# RP2350.net
KiCad netlist of a schematic drawn in EasyEDA Pro
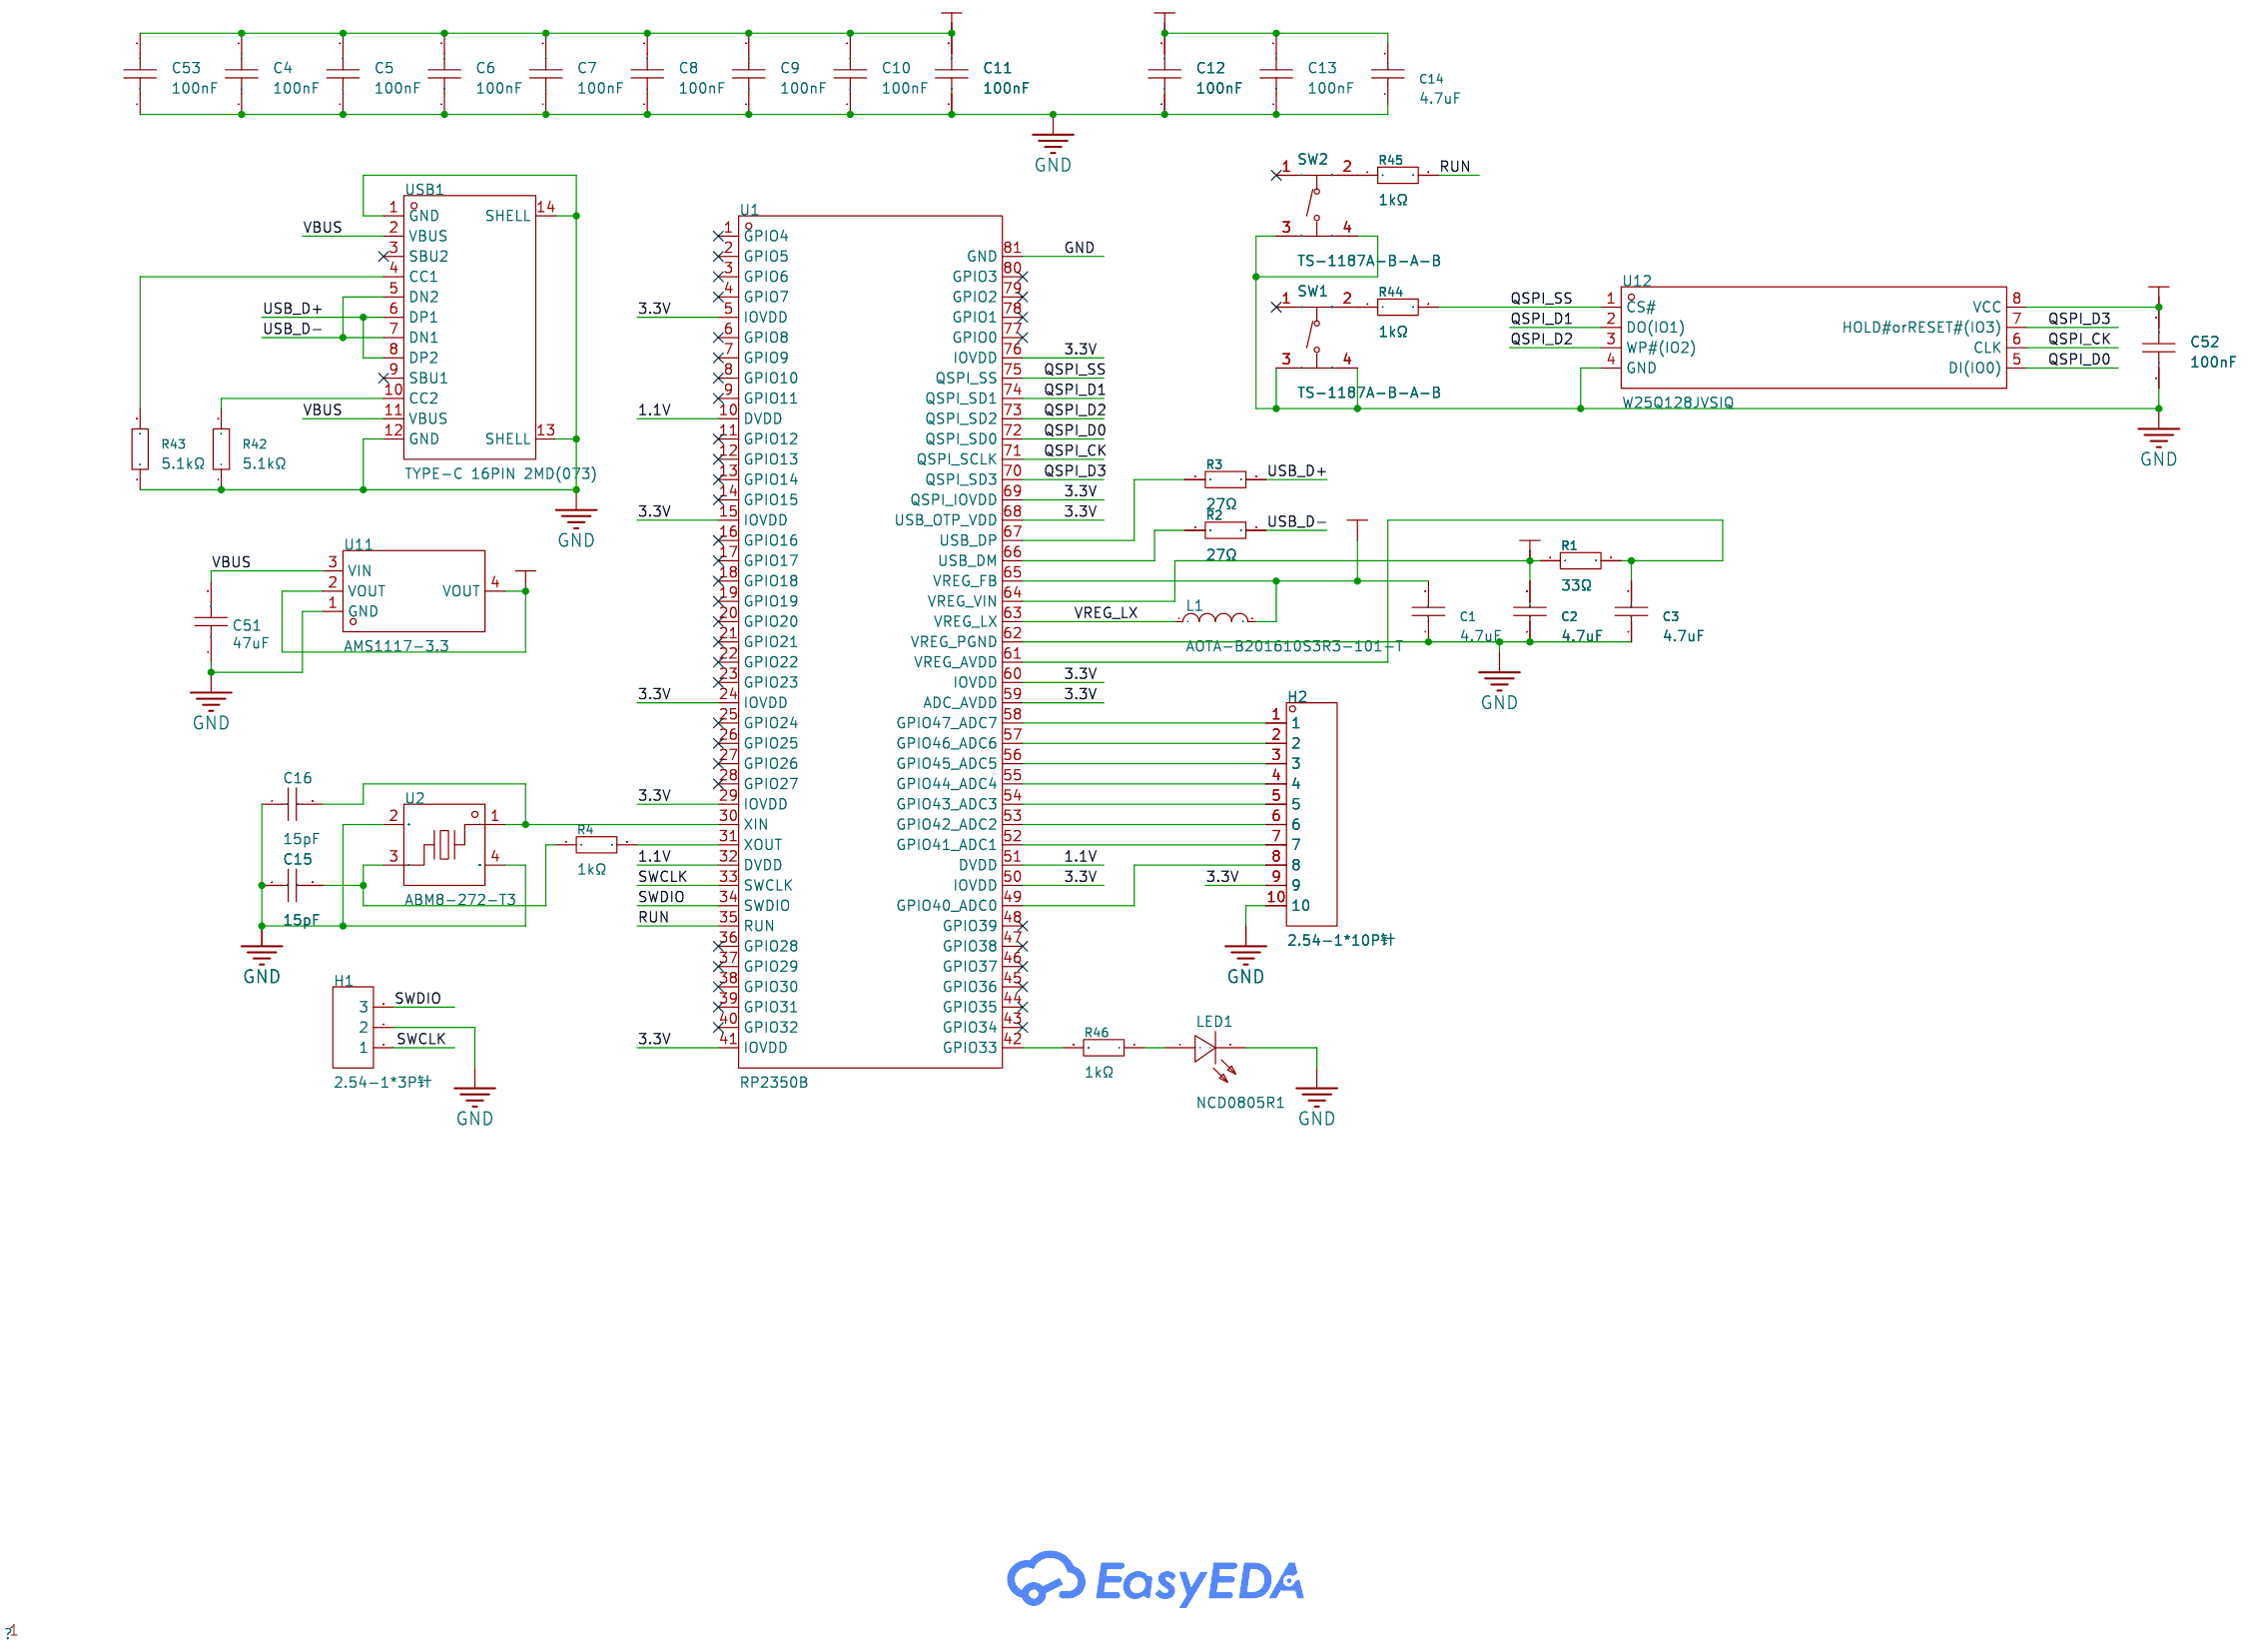
[diagram p0: schematic sheet]

(export (version "E")
  (design (tool "Eeschema 10.0.6"))
  (components
    (comp (ref "C1")
      (value "4.7uF")
      (footprint "easyedapro:C0402")
      (fields
        (field (name "Manufacturer Part") "CL05A475MP5NRNC")
        (field (name "Manufacturer") "SAMSUNG(三星)")
      )
      (libsource (lib "easyedapro") (part "CL05A475MP5NRNC"))
    )
    (comp (ref "C2")
      (value "4.7uF")
      (footprint "easyedapro:C0402")
      (fields
        (field (name "Manufacturer Part") "CL05A475MP5NRNC")
        (field (name "Manufacturer") "SAMSUNG(三星)")
      )
      (libsource (lib "easyedapro") (part "CL05A475MP5NRNC"))
    )
    (comp (ref "C3")
      (value "4.7uF")
      (footprint "easyedapro:C0402")
      (fields
        (field (name "Manufacturer Part") "CL05A475MP5NRNC")
        (field (name "Manufacturer") "SAMSUNG(三星)")
      )
      (libsource (lib "easyedapro") (part "CL05A475MP5NRNC"))
    )
    (comp (ref "C4")
      (value "100nF")
      (footprint "easyedapro:C0402")
      (fields
        (field (name "Manufacturer Part") "CL05B104KO5NNNC")
        (field (name "Manufacturer") "SAMSUNG(三星)")
      )
      (libsource (lib "easyedapro") (part "CL05B104KO5NNNC"))
    )
    (comp (ref "C5")
      (value "100nF")
      (footprint "easyedapro:C0402")
      (fields
        (field (name "Manufacturer Part") "CL05B104KO5NNNC")
        (field (name "Manufacturer") "SAMSUNG(三星)")
      )
      (libsource (lib "easyedapro") (part "CL05B104KO5NNNC"))
    )
    (comp (ref "C6")
      (value "100nF")
      (footprint "easyedapro:C0402")
      (fields
        (field (name "Manufacturer Part") "CL05B104KO5NNNC")
        (field (name "Manufacturer") "SAMSUNG(三星)")
      )
      (libsource (lib "easyedapro") (part "CL05B104KO5NNNC"))
    )
    (comp (ref "C7")
      (value "100nF")
      (footprint "easyedapro:C0402")
      (fields
        (field (name "Manufacturer Part") "CL05B104KO5NNNC")
        (field (name "Manufacturer") "SAMSUNG(三星)")
      )
      (libsource (lib "easyedapro") (part "CL05B104KO5NNNC"))
    )
    (comp (ref "C8")
      (value "100nF")
      (footprint "easyedapro:C0402")
      (fields
        (field (name "Manufacturer Part") "CL05B104KO5NNNC")
        (field (name "Manufacturer") "SAMSUNG(三星)")
      )
      (libsource (lib "easyedapro") (part "CL05B104KO5NNNC"))
    )
    (comp (ref "C9")
      (value "100nF")
      (footprint "easyedapro:C0402")
      (fields
        (field (name "Manufacturer Part") "CL05B104KO5NNNC")
        (field (name "Manufacturer") "SAMSUNG(三星)")
      )
      (libsource (lib "easyedapro") (part "CL05B104KO5NNNC"))
    )
    (comp (ref "C10")
      (value "100nF")
      (footprint "easyedapro:C0402")
      (fields
        (field (name "Manufacturer Part") "CL05B104KO5NNNC")
        (field (name "Manufacturer") "SAMSUNG(三星)")
      )
      (libsource (lib "easyedapro") (part "CL05B104KO5NNNC"))
    )
    (comp (ref "C11")
      (value "100nF")
      (footprint "easyedapro:C0402")
      (fields
        (field (name "Manufacturer Part") "CL05B104KO5NNNC")
        (field (name "Manufacturer") "SAMSUNG(三星)")
      )
      (libsource (lib "easyedapro") (part "CL05B104KO5NNNC"))
    )
    (comp (ref "C12")
      (value "100nF")
      (footprint "easyedapro:C0402")
      (fields
        (field (name "Manufacturer Part") "CL05B104KO5NNNC")
        (field (name "Manufacturer") "SAMSUNG(三星)")
      )
      (libsource (lib "easyedapro") (part "CL05B104KO5NNNC"))
    )
    (comp (ref "C13")
      (value "100nF")
      (footprint "easyedapro:C0402")
      (fields
        (field (name "Manufacturer Part") "CL05B104KO5NNNC")
        (field (name "Manufacturer") "SAMSUNG(三星)")
      )
      (libsource (lib "easyedapro") (part "CL05B104KO5NNNC"))
    )
    (comp (ref "C14")
      (value "4.7uF")
      (footprint "easyedapro:C0402")
      (fields
        (field (name "Manufacturer Part") "CL05A475MP5NRNC")
        (field (name "Manufacturer") "SAMSUNG(三星)")
      )
      (libsource (lib "easyedapro") (part "CL05A475MP5NRNC"))
    )
    (comp (ref "C15")
      (value "15pF")
      (footprint "easyedapro:C0402")
      (fields (field (name "Manufacturer Part") "0402CG150J500NT") (field (name "Manufacturer") "FH(风华)"))
      (libsource (lib "easyedapro") (part "0402CG150J500NT"))
    )
    (comp (ref "C16")
      (value "15pF")
      (footprint "easyedapro:C0402")
      (fields (field (name "Manufacturer Part") "0402CG150J500NT") (field (name "Manufacturer") "FH(风华)"))
      (libsource (lib "easyedapro") (part "0402CG150J500NT"))
    )
    (comp (ref "C51")
      (value "47uF")
      (footprint "easyedapro:C1206")
      (fields (field (name "Manufacturer Part") "CL31A476MPHNNNE") (field (name "Manufacturer") "SAMSUNG"))
      (libsource (lib "easyedapro") (part "47uF"))
    )
    (comp (ref "C52")
      (value "100nF")
      (footprint "easyedapro:C0402")
      (fields
        (field (name "Manufacturer Part") "CL05B104KO5NNNC")
        (field (name "Manufacturer") "SAMSUNG(三星)")
      )
      (libsource (lib "easyedapro") (part "CL05B104KO5NNNC"))
    )
    (comp (ref "C53")
      (value "100nF")
      (footprint "easyedapro:C0402")
      (fields
        (field (name "Manufacturer Part") "CL05B104KO5NNNC")
        (field (name "Manufacturer") "SAMSUNG(三星)")
      )
      (libsource (lib "easyedapro") (part "CL05B104KO5NNNC"))
    )
    (comp (ref "H1")
      (value "2.54-1*3P针")
      (footprint "easyedapro:HDR-TH_3P-P2.54-V-M-1")
      (fields (field (name "Manufacturer") "BOOMELE(博穆精密)"))
      (libsource (lib "easyedapro") (part "Header-Male-2.54_1x3"))
    )
    (comp (ref "H2")
      (value "2.54-1*10P针")
      (footprint "easyedapro:HDR-TH_10P-P2.54-V-M-1")
      (fields (field (name "Manufacturer") "BOOMELE(博穆精密)"))
      (libsource (lib "easyedapro") (part "Header-Male-2.54_1x10"))
    )
    (comp (ref "L1")
      (value "AOTA-B201610S3R3-101-T")
      (footprint "easyedapro:IND-SMD_L2.0-W1.6_AOTA-B201610S3R3-101-T")
      (fields (field (name "Manufacturer") "ABRACON"))
      (libsource (lib "easyedapro") (part "AOTA-B201610S3R3-101-T"))
    )
    (comp (ref "LED1")
      (value "NCD0805R1")
      (footprint "easyedapro:LED0805-R-RD")
      (fields (field (name "Manufacturer") "国星光电"))
      (libsource (lib "easyedapro") (part "FC-2012HRK-620D"))
    )
    (comp (ref "R1")
      (value "33Ω")
      (footprint "easyedapro:R0402")
      (fields
        (field (name "Manufacturer Part") "0402WGF330JTCE")
        (field (name "Manufacturer") "UNI-ROYAL(厚声)")
      )
      (libsource (lib "easyedapro") (part "0402WGF330JTCE"))
    )
    (comp (ref "R2")
      (value "27Ω")
      (footprint "easyedapro:R0402")
      (fields
        (field (name "Manufacturer Part") "0402WGF270JTCE")
        (field (name "Manufacturer") "UNI-ROYAL(厚声)")
      )
      (libsource (lib "easyedapro") (part "0402WGF270JTCE"))
    )
    (comp (ref "R3")
      (value "27Ω")
      (footprint "easyedapro:R0402")
      (fields (field (name "Manufacturer Part") "F") (field (name "Manufacturer") "UNI-ROYAL(厚声)"))
      (libsource (lib "easyedapro") (part "0402WGF270JTCE"))
    )
    (comp (ref "R4")
      (value "1kΩ")
      (footprint "easyedapro:R0402")
      (fields
        (field (name "Manufacturer Part") "0402WGF1001TCE")
        (field (name "Manufacturer") "UNI-ROYAL(厚声)")
      )
      (libsource (lib "easyedapro") (part "0402WGF1001TCE"))
    )
    (comp (ref "R42")
      (value "5.1kΩ")
      (footprint "easyedapro:R0402")
      (fields
        (field (name "Manufacturer Part") "0402WGF5101TCE")
        (field (name "Manufacturer") "UNI-ROYAL(厚声)")
      )
      (libsource (lib "easyedapro") (part "0402WGF5101TCE"))
    )
    (comp (ref "R43")
      (value "5.1kΩ")
      (footprint "easyedapro:R0402")
      (fields
        (field (name "Manufacturer Part") "0402WGF5101TCE")
        (field (name "Manufacturer") "UNI-ROYAL(厚声)")
      )
      (libsource (lib "easyedapro") (part "0402WGF5101TCE"))
    )
    (comp (ref "R44")
      (value "1kΩ")
      (footprint "easyedapro:R0402")
      (fields
        (field (name "Manufacturer Part") "0402WGF1001TCE")
        (field (name "Manufacturer") "UNI-ROYAL(厚声)")
      )
      (libsource (lib "easyedapro") (part "0402WGF1001TCE"))
    )
    (comp (ref "R45")
      (value "1kΩ")
      (footprint "easyedapro:R0402")
      (fields
        (field (name "Manufacturer Part") "0402WGF1001TCE")
        (field (name "Manufacturer") "UNI-ROYAL(厚声)")
      )
      (libsource (lib "easyedapro") (part "0402WGF1001TCE"))
    )
    (comp (ref "R46")
      (value "1kΩ")
      (footprint "easyedapro:R0402")
      (fields
        (field (name "Manufacturer Part") "0402WGF1001TCE")
        (field (name "Manufacturer") "UNI-ROYAL(厚声)")
      )
      (libsource (lib "easyedapro") (part "0402WGF1001TCE"))
    )
    (comp (ref "SW1")
      (value "TS-1187A-B-A-B")
      (footprint "easyedapro:SW-SMD_4P-L5.1-W5.1-P3.70-LS6.5-TL_H1.5")
      (fields (field (name "Manufacturer") "XKB Connectivity(中国星坤)"))
      (libsource (lib "easyedapro") (part "TS-1187A-B-A-B"))
    )
    (comp (ref "SW2")
      (value "TS-1187A-B-A-B")
      (footprint "easyedapro:SW-SMD_4P-L5.1-W5.1-P3.70-LS6.5-TL_H1.5")
      (fields (field (name "Manufacturer") "XKB Connectivity(中国星坤)"))
      (libsource (lib "easyedapro") (part "TS-1187A-B-A-B"))
    )
    (comp (ref "U1")
      (value "RP2350B")
      (footprint "easyedapro:QFN-80_L10.0-W10.0-P0.40-TL-EP3.4")
      (fields (field (name "Manufacturer") "Raspberry Pi(树莓派)"))
      (libsource (lib "easyedapro") (part "RP2350B_C42415655"))
    )
    (comp (ref "U2")
      (value "ABM8-272-T3")
      (footprint "easyedapro:CRYSTAL-SMD_4P-L3.2-W2.5-BL")
      (fields (field (name "Manufacturer") "ABRACON"))
      (libsource (lib "easyedapro") (part "ABM8-272-T3_C20625731"))
    )
    (comp (ref "U11")
      (value "AMS1117-3.3")
      (footprint "easyedapro:SOT-223-3_L6.5-W3.4-P2.30-LS7.0-BR")
      (fields (field (name "Manufacturer") "AMS"))
      (libsource (lib "easyedapro") (part "AMS1117-3.3"))
    )
    (comp (ref "U12")
      (value "W25Q128JVSIQ")
      (footprint "easyedapro:SOIC-8_L5.3-W5.3-P1.27-LS8.0-BL")
      (fields (field (name "Manufacturer") "WINBOND(华邦)"))
      (libsource (lib "easyedapro") (part "W25Q128JVSIQ"))
    )
    (comp (ref "USB1")
      (value "TYPE-C 16PIN 2MD(073)")
      (footprint "easyedapro:USB-C-SMD_TYPE-C-6PIN-2MD-073")
      (fields (field (name "Manufacturer") "SHOU HAN(首韩)"))
      (libsource (lib "easyedapro") (part "TYPE-C 16PIN 2MD(073)"))
    )
  )
  (nets
    (net (code "1") (name "/QSPI_CK") (class "Default")
      (node (ref "U1") (pin "71") (pinfunction "QSPI_SCLK_71") (pintype "unspecified"))
      (node (ref "U12") (pin "6") (pinfunction "CLK_6") (pintype "unspecified"))
    )
    (net (code "2") (name "/QSPI_D0") (class "Default")
      (node (ref "U1") (pin "72") (pinfunction "QSPI_SD0_72") (pintype "unspecified"))
      (node (ref "U12") (pin "5") (pinfunction "DI(IO0)_5") (pintype "unspecified"))
    )
    (net (code "3") (name "/QSPI_D1") (class "Default")
      (node (ref "U1") (pin "74") (pinfunction "QSPI_SD1_74") (pintype "unspecified"))
      (node (ref "U12") (pin "2") (pinfunction "DO(IO1)_2") (pintype "unspecified"))
    )
    (net (code "4") (name "/QSPI_D2") (class "Default")
      (node (ref "U1") (pin "73") (pinfunction "QSPI_SD2_73") (pintype "unspecified"))
      (node (ref "U12") (pin "3") (pinfunction "WP#(IO2)_3") (pintype "unspecified"))
    )
    (net (code "5") (name "/QSPI_D3") (class "Default")
      (node (ref "U1") (pin "70") (pinfunction "QSPI_SD3_70") (pintype "unspecified"))
      (node (ref "U12") (pin "7") (pinfunction "HOLD#orRESET#(IO3)_7") (pintype "unspecified"))
    )
    (net (code "6") (name "/QSPI_SS") (class "Default")
      (node (ref "R44") (pin "2") (pinfunction "2_2") (pintype "input"))
      (node (ref "U1") (pin "75") (pinfunction "QSPI_SS_75") (pintype "unspecified"))
      (node (ref "U12") (pin "1") (pinfunction "CS#_1") (pintype "unspecified"))
    )
    (net (code "7") (name "/RUN") (class "Default")
      (node (ref "R45") (pin "2") (pinfunction "2_2") (pintype "input"))
      (node (ref "U1") (pin "35") (pinfunction "RUN_35") (pintype "unspecified"))
    )
    (net (code "8") (name "/SWCLK") (class "Default")
      (node (ref "H1") (pin "1") (pinfunction "1_1") (pintype "input"))
      (node (ref "U1") (pin "33") (pinfunction "SWCLK_33") (pintype "unspecified"))
    )
    (net (code "9") (name "/SWDIO") (class "Default")
      (node (ref "H1") (pin "3") (pinfunction "3_3") (pintype "input"))
      (node (ref "U1") (pin "34") (pinfunction "SWDIO_34") (pintype "unspecified"))
    )
    (net (code "10") (name "/USB_D+") (class "Default")
      (node (ref "R3") (pin "2") (pinfunction "2_2") (pintype "input"))
      (node (ref "USB1") (pin "6") (pinfunction "DP1_6") (pintype "unspecified"))
      (node (ref "USB1") (pin "8") (pinfunction "DP2_8") (pintype "unspecified"))
    )
    (net (code "11") (name "/USB_D-") (class "Default")
      (node (ref "R2") (pin "2") (pinfunction "2_2") (pintype "input"))
      (node (ref "USB1") (pin "5") (pinfunction "DN2_5") (pintype "unspecified"))
      (node (ref "USB1") (pin "7") (pinfunction "DN1_7") (pintype "unspecified"))
    )
    (net (code "12") (name "/VBUS") (class "Default")
      (node (ref "C51") (pin "2") (pinfunction "2_2") (pintype "unspecified"))
      (node (ref "U11") (pin "3") (pinfunction "VIN_3") (pintype "unspecified"))
      (node (ref "USB1") (pin "11") (pinfunction "VBUS_11") (pintype "unspecified"))
      (node (ref "USB1") (pin "2") (pinfunction "VBUS_2") (pintype "unspecified"))
    )
    (net (code "13") (name "/VREG_LX") (class "Default")
      (node (ref "L1") (pin "1") (pinfunction "1_1") (pintype "unspecified"))
      (node (ref "U1") (pin "63") (pinfunction "VREG_LX_63") (pintype "unspecified"))
    )
    (net (code "14") (name "1.1V") (class "Default")
      (node (ref "C1") (pin "2") (pinfunction "2_2") (pintype "input"))
      (node (ref "C12") (pin "2") (pinfunction "2_2") (pintype "unspecified"))
      (node (ref "C13") (pin "2") (pinfunction "2_2") (pintype "unspecified"))
      (node (ref "C14") (pin "2") (pinfunction "2_2") (pintype "input"))
      (node (ref "L1") (pin "2") (pinfunction "2_2") (pintype "unspecified"))
      (node (ref "U1") (pin "10") (pinfunction "DVDD_10") (pintype "unspecified"))
      (node (ref "U1") (pin "32") (pinfunction "DVDD_32") (pintype "unspecified"))
      (node (ref "U1") (pin "51") (pinfunction "DVDD_51") (pintype "unspecified"))
      (node (ref "U1") (pin "65") (pinfunction "VREG_FB_65") (pintype "unspecified"))
    )
    (net (code "15") (name "3.3V") (class "Default")
      (node (ref "C10") (pin "2") (pinfunction "2_2") (pintype "unspecified"))
      (node (ref "C11") (pin "2") (pinfunction "2_2") (pintype "unspecified"))
      (node (ref "C2") (pin "2") (pinfunction "2_2") (pintype "input"))
      (node (ref "C4") (pin "2") (pinfunction "2_2") (pintype "unspecified"))
      (node (ref "C5") (pin "2") (pinfunction "2_2") (pintype "unspecified"))
      (node (ref "C52") (pin "2") (pinfunction "2_2") (pintype "unspecified"))
      (node (ref "C53") (pin "2") (pinfunction "2_2") (pintype "unspecified"))
      (node (ref "C6") (pin "2") (pinfunction "2_2") (pintype "unspecified"))
      (node (ref "C7") (pin "2") (pinfunction "2_2") (pintype "unspecified"))
      (node (ref "C8") (pin "2") (pinfunction "2_2") (pintype "unspecified"))
      (node (ref "C9") (pin "2") (pinfunction "2_2") (pintype "unspecified"))
      (node (ref "H2") (pin "9") (pinfunction "9_9") (pintype "input"))
      (node (ref "R1") (pin "1") (pinfunction "1_1") (pintype "input"))
      (node (ref "U1") (pin "15") (pinfunction "IOVDD_15") (pintype "unspecified"))
      (node (ref "U1") (pin "24") (pinfunction "IOVDD_24") (pintype "unspecified"))
      (node (ref "U1") (pin "29") (pinfunction "IOVDD_29") (pintype "unspecified"))
      (node (ref "U1") (pin "41") (pinfunction "IOVDD_41") (pintype "unspecified"))
      (node (ref "U1") (pin "5") (pinfunction "IOVDD_5") (pintype "unspecified"))
      (node (ref "U1") (pin "50") (pinfunction "IOVDD_50") (pintype "unspecified"))
      (node (ref "U1") (pin "59") (pinfunction "ADC_AVDD_59") (pintype "unspecified"))
      (node (ref "U1") (pin "60") (pinfunction "IOVDD_60") (pintype "unspecified"))
      (node (ref "U1") (pin "64") (pinfunction "VREG_VIN_64") (pintype "unspecified"))
      (node (ref "U1") (pin "68") (pinfunction "USB_OTP_VDD_68") (pintype "unspecified"))
      (node (ref "U1") (pin "69") (pinfunction "QSPI_IOVDD_69") (pintype "unspecified"))
      (node (ref "U1") (pin "76") (pinfunction "IOVDD_76") (pintype "unspecified"))
      (node (ref "U11") (pin "2") (pinfunction "VOUT_2") (pintype "unspecified"))
      (node (ref "U11") (pin "4") (pinfunction "VOUT_4") (pintype "unspecified"))
      (node (ref "U12") (pin "8") (pinfunction "VCC_8") (pintype "unspecified"))
    )
    (net (code "16") (name "GND") (class "Default")
      (node (ref "C1") (pin "1") (pinfunction "1_1") (pintype "input"))
      (node (ref "C10") (pin "1") (pinfunction "1_1") (pintype "unspecified"))
      (node (ref "C11") (pin "1") (pinfunction "1_1") (pintype "unspecified"))
      (node (ref "C12") (pin "1") (pinfunction "1_1") (pintype "unspecified"))
      (node (ref "C13") (pin "1") (pinfunction "1_1") (pintype "unspecified"))
      (node (ref "C14") (pin "1") (pinfunction "1_1") (pintype "input"))
      (node (ref "C15") (pin "1") (pinfunction "1_1") (pintype "input"))
      (node (ref "C16") (pin "1") (pinfunction "1_1") (pintype "input"))
      (node (ref "C2") (pin "1") (pinfunction "1_1") (pintype "input"))
      (node (ref "C3") (pin "1") (pinfunction "1_1") (pintype "input"))
      (node (ref "C4") (pin "1") (pinfunction "1_1") (pintype "unspecified"))
      (node (ref "C5") (pin "1") (pinfunction "1_1") (pintype "unspecified"))
      (node (ref "C51") (pin "1") (pinfunction "1_1") (pintype "unspecified"))
      (node (ref "C52") (pin "1") (pinfunction "1_1") (pintype "unspecified"))
      (node (ref "C53") (pin "1") (pinfunction "1_1") (pintype "unspecified"))
      (node (ref "C6") (pin "1") (pinfunction "1_1") (pintype "unspecified"))
      (node (ref "C7") (pin "1") (pinfunction "1_1") (pintype "unspecified"))
      (node (ref "C8") (pin "1") (pinfunction "1_1") (pintype "unspecified"))
      (node (ref "C9") (pin "1") (pinfunction "1_1") (pintype "unspecified"))
      (node (ref "H1") (pin "2") (pinfunction "2_2") (pintype "input"))
      (node (ref "H2") (pin "10") (pinfunction "10_10") (pintype "input"))
      (node (ref "LED1") (pin "2") (pinfunction "-_2") (pintype "unspecified"))
      (node (ref "R42") (pin "1") (pinfunction "1_1") (pintype "input"))
      (node (ref "R43") (pin "1") (pinfunction "1_1") (pintype "input"))
      (node (ref "SW1") (pin "3") (pinfunction "C_3") (pintype "unspecified"))
      (node (ref "SW1") (pin "4") (pinfunction "D_4") (pintype "unspecified"))
      (node (ref "SW2") (pin "3") (pinfunction "C_3") (pintype "unspecified"))
      (node (ref "SW2") (pin "4") (pinfunction "D_4") (pintype "unspecified"))
      (node (ref "U1") (pin "62") (pinfunction "VREG_PGND_62") (pintype "unspecified"))
      (node (ref "U1") (pin "81") (pinfunction "GND_81") (pintype "unspecified"))
      (node (ref "U11") (pin "1") (pinfunction "GND_1") (pintype "unspecified"))
      (node (ref "U12") (pin "4") (pinfunction "GND_4") (pintype "unspecified"))
      (node (ref "U2") (pin "2") (pinfunction "GND_2") (pintype "input"))
      (node (ref "U2") (pin "4") (pinfunction "GND_4") (pintype "input"))
      (node (ref "USB1") (pin "1") (pinfunction "GND_1") (pintype "unspecified"))
      (node (ref "USB1") (pin "12") (pinfunction "GND_12") (pintype "unspecified"))
      (node (ref "USB1") (pin "13") (pinfunction "SHELL_13") (pintype "unspecified"))
      (node (ref "USB1") (pin "14") (pinfunction "SHELL_14") (pintype "unspecified"))
    )
    (net (code "17") (name "Net-(C15-Pad2)") (class "Default")
      (node (ref "C15") (pin "2") (pinfunction "2_2") (pintype "input"))
      (node (ref "R4") (pin "1") (pinfunction "1_1") (pintype "input"))
      (node (ref "U2") (pin "3") (pinfunction "3_3") (pintype "input"))
    )
    (net (code "18") (name "Net-(LED1-+)") (class "Default")
      (node (ref "LED1") (pin "1") (pinfunction "+_1") (pintype "unspecified"))
      (node (ref "R46") (pin "1") (pinfunction "1_1") (pintype "input"))
    )
    (net (code "19") (name "Net-(SW1-B)") (class "Default")
      (node (ref "R44") (pin "1") (pinfunction "1_1") (pintype "input"))
      (node (ref "SW1") (pin "2") (pinfunction "B_2") (pintype "unspecified"))
    )
    (net (code "20") (name "Net-(SW2-B)") (class "Default")
      (node (ref "R45") (pin "1") (pinfunction "1_1") (pintype "input"))
      (node (ref "SW2") (pin "2") (pinfunction "B_2") (pintype "unspecified"))
    )
    (net (code "21") (name "Net-(U1-GPIO33)") (class "Default")
      (node (ref "R46") (pin "2") (pinfunction "2_2") (pintype "input"))
      (node (ref "U1") (pin "42") (pinfunction "GPIO33_42") (pintype "unspecified"))
    )
    (net (code "22") (name "Net-(U1-GPIO40_ADC0)") (class "Default")
      (node (ref "H2") (pin "8") (pinfunction "8_8") (pintype "input"))
      (node (ref "U1") (pin "49") (pinfunction "GPIO40_ADC0_49") (pintype "unspecified"))
    )
    (net (code "23") (name "Net-(U1-GPIO41_ADC1)") (class "Default")
      (node (ref "H2") (pin "7") (pinfunction "7_7") (pintype "input"))
      (node (ref "U1") (pin "52") (pinfunction "GPIO41_ADC1_52") (pintype "unspecified"))
    )
    (net (code "24") (name "Net-(U1-GPIO42_ADC2)") (class "Default")
      (node (ref "H2") (pin "6") (pinfunction "6_6") (pintype "input"))
      (node (ref "U1") (pin "53") (pinfunction "GPIO42_ADC2_53") (pintype "unspecified"))
    )
    (net (code "25") (name "Net-(U1-GPIO43_ADC3)") (class "Default")
      (node (ref "H2") (pin "5") (pinfunction "5_5") (pintype "input"))
      (node (ref "U1") (pin "54") (pinfunction "GPIO43_ADC3_54") (pintype "unspecified"))
    )
    (net (code "26") (name "Net-(U1-GPIO44_ADC4)") (class "Default")
      (node (ref "H2") (pin "4") (pinfunction "4_4") (pintype "input"))
      (node (ref "U1") (pin "55") (pinfunction "GPIO44_ADC4_55") (pintype "unspecified"))
    )
    (net (code "27") (name "Net-(U1-GPIO45_ADC5)") (class "Default")
      (node (ref "H2") (pin "3") (pinfunction "3_3") (pintype "input"))
      (node (ref "U1") (pin "56") (pinfunction "GPIO45_ADC5_56") (pintype "unspecified"))
    )
    (net (code "28") (name "Net-(U1-GPIO46_ADC6)") (class "Default")
      (node (ref "H2") (pin "2") (pinfunction "2_2") (pintype "input"))
      (node (ref "U1") (pin "57") (pinfunction "GPIO46_ADC6_57") (pintype "unspecified"))
    )
    (net (code "29") (name "Net-(U1-GPIO47_ADC7)") (class "Default")
      (node (ref "H2") (pin "1") (pinfunction "1_1") (pintype "input"))
      (node (ref "U1") (pin "58") (pinfunction "GPIO47_ADC7_58") (pintype "unspecified"))
    )
    (net (code "30") (name "Net-(U1-USB_DM)") (class "Default")
      (node (ref "R2") (pin "1") (pinfunction "1_1") (pintype "input"))
      (node (ref "U1") (pin "66") (pinfunction "USB_DM_66") (pintype "unspecified"))
    )
    (net (code "31") (name "Net-(U1-USB_DP)") (class "Default")
      (node (ref "R3") (pin "1") (pinfunction "1_1") (pintype "input"))
      (node (ref "U1") (pin "67") (pinfunction "USB_DP_67") (pintype "unspecified"))
    )
    (net (code "32") (name "Net-(U1-VREG_AVDD)") (class "Default")
      (node (ref "C3") (pin "2") (pinfunction "2_2") (pintype "input"))
      (node (ref "R1") (pin "2") (pinfunction "2_2") (pintype "input"))
      (node (ref "U1") (pin "61") (pinfunction "VREG_AVDD_61") (pintype "unspecified"))
    )
    (net (code "33") (name "Net-(U1-XIN)") (class "Default")
      (node (ref "C16") (pin "2") (pinfunction "2_2") (pintype "input"))
      (node (ref "U1") (pin "30") (pinfunction "XIN_30") (pintype "unspecified"))
      (node (ref "U2") (pin "1") (pinfunction "1_1") (pintype "input"))
    )
    (net (code "34") (name "Net-(U1-XOUT)") (class "Default")
      (node (ref "R4") (pin "2") (pinfunction "2_2") (pintype "input"))
      (node (ref "U1") (pin "31") (pinfunction "XOUT_31") (pintype "unspecified"))
    )
    (net (code "35") (name "Net-(USB1-CC1)") (class "Default")
      (node (ref "R43") (pin "2") (pinfunction "2_2") (pintype "input"))
      (node (ref "USB1") (pin "4") (pinfunction "CC1_4") (pintype "unspecified"))
    )
    (net (code "36") (name "Net-(USB1-CC2)") (class "Default")
      (node (ref "R42") (pin "2") (pinfunction "2_2") (pintype "input"))
      (node (ref "USB1") (pin "10") (pinfunction "CC2_10") (pintype "unspecified"))
    )
    (net (code "37") (name "unconnected-(SW1-A-Pad1)") (class "Default")
      (node (ref "SW1") (pin "1") (pinfunction "A_1") (pintype "unspecified+no_connect"))
    )
    (net (code "38") (name "unconnected-(SW2-A-Pad1)") (class "Default")
      (node (ref "SW2") (pin "1") (pinfunction "A_1") (pintype "unspecified+no_connect"))
    )
    (net (code "39") (name "unconnected-(U1-GPIO0-Pad77)") (class "Default")
      (node (ref "U1") (pin "77") (pinfunction "GPIO0_77") (pintype "unspecified+no_connect"))
    )
    (net (code "40") (name "unconnected-(U1-GPIO1-Pad78)") (class "Default")
      (node (ref "U1") (pin "78") (pinfunction "GPIO1_78") (pintype "unspecified+no_connect"))
    )
    (net (code "41") (name "unconnected-(U1-GPIO2-Pad79)") (class "Default")
      (node (ref "U1") (pin "79") (pinfunction "GPIO2_79") (pintype "unspecified+no_connect"))
    )
    (net (code "42") (name "unconnected-(U1-GPIO3-Pad80)") (class "Default")
      (node (ref "U1") (pin "80") (pinfunction "GPIO3_80") (pintype "unspecified+no_connect"))
    )
    (net (code "43") (name "unconnected-(U1-GPIO4-Pad1)") (class "Default")
      (node (ref "U1") (pin "1") (pinfunction "GPIO4_1") (pintype "unspecified+no_connect"))
    )
    (net (code "44") (name "unconnected-(U1-GPIO5-Pad2)") (class "Default")
      (node (ref "U1") (pin "2") (pinfunction "GPIO5_2") (pintype "unspecified+no_connect"))
    )
    (net (code "45") (name "unconnected-(U1-GPIO6-Pad3)") (class "Default")
      (node (ref "U1") (pin "3") (pinfunction "GPIO6_3") (pintype "unspecified+no_connect"))
    )
    (net (code "46") (name "unconnected-(U1-GPIO7-Pad4)") (class "Default")
      (node (ref "U1") (pin "4") (pinfunction "GPIO7_4") (pintype "unspecified+no_connect"))
    )
    (net (code "47") (name "unconnected-(U1-GPIO8-Pad6)") (class "Default")
      (node (ref "U1") (pin "6") (pinfunction "GPIO8_6") (pintype "unspecified+no_connect"))
    )
    (net (code "48") (name "unconnected-(U1-GPIO9-Pad7)") (class "Default")
      (node (ref "U1") (pin "7") (pinfunction "GPIO9_7") (pintype "unspecified+no_connect"))
    )
    (net (code "49") (name "unconnected-(U1-GPIO10-Pad8)") (class "Default")
      (node (ref "U1") (pin "8") (pinfunction "GPIO10_8") (pintype "unspecified+no_connect"))
    )
    (net (code "50") (name "unconnected-(U1-GPIO11-Pad9)") (class "Default")
      (node (ref "U1") (pin "9") (pinfunction "GPIO11_9") (pintype "unspecified+no_connect"))
    )
    (net (code "51") (name "unconnected-(U1-GPIO12-Pad11)") (class "Default")
      (node (ref "U1") (pin "11") (pinfunction "GPIO12_11") (pintype "unspecified+no_connect"))
    )
    (net (code "52") (name "unconnected-(U1-GPIO13-Pad12)") (class "Default")
      (node (ref "U1") (pin "12") (pinfunction "GPIO13_12") (pintype "unspecified+no_connect"))
    )
    (net (code "53") (name "unconnected-(U1-GPIO14-Pad13)") (class "Default")
      (node (ref "U1") (pin "13") (pinfunction "GPIO14_13") (pintype "unspecified+no_connect"))
    )
    (net (code "54") (name "unconnected-(U1-GPIO15-Pad14)") (class "Default")
      (node (ref "U1") (pin "14") (pinfunction "GPIO15_14") (pintype "unspecified+no_connect"))
    )
    (net (code "55") (name "unconnected-(U1-GPIO16-Pad16)") (class "Default")
      (node (ref "U1") (pin "16") (pinfunction "GPIO16_16") (pintype "unspecified+no_connect"))
    )
    (net (code "56") (name "unconnected-(U1-GPIO17-Pad17)") (class "Default")
      (node (ref "U1") (pin "17") (pinfunction "GPIO17_17") (pintype "unspecified+no_connect"))
    )
    (net (code "57") (name "unconnected-(U1-GPIO18-Pad18)") (class "Default")
      (node (ref "U1") (pin "18") (pinfunction "GPIO18_18") (pintype "unspecified+no_connect"))
    )
    (net (code "58") (name "unconnected-(U1-GPIO19-Pad19)") (class "Default")
      (node (ref "U1") (pin "19") (pinfunction "GPIO19_19") (pintype "unspecified+no_connect"))
    )
    (net (code "59") (name "unconnected-(U1-GPIO20-Pad20)") (class "Default")
      (node (ref "U1") (pin "20") (pinfunction "GPIO20_20") (pintype "unspecified+no_connect"))
    )
    (net (code "60") (name "unconnected-(U1-GPIO21-Pad21)") (class "Default")
      (node (ref "U1") (pin "21") (pinfunction "GPIO21_21") (pintype "unspecified+no_connect"))
    )
    (net (code "61") (name "unconnected-(U1-GPIO22-Pad22)") (class "Default")
      (node (ref "U1") (pin "22") (pinfunction "GPIO22_22") (pintype "unspecified+no_connect"))
    )
    (net (code "62") (name "unconnected-(U1-GPIO23-Pad23)") (class "Default")
      (node (ref "U1") (pin "23") (pinfunction "GPIO23_23") (pintype "unspecified+no_connect"))
    )
    (net (code "63") (name "unconnected-(U1-GPIO24-Pad25)") (class "Default")
      (node (ref "U1") (pin "25") (pinfunction "GPIO24_25") (pintype "unspecified+no_connect"))
    )
    (net (code "64") (name "unconnected-(U1-GPIO25-Pad26)") (class "Default")
      (node (ref "U1") (pin "26") (pinfunction "GPIO25_26") (pintype "unspecified+no_connect"))
    )
    (net (code "65") (name "unconnected-(U1-GPIO26-Pad27)") (class "Default")
      (node (ref "U1") (pin "27") (pinfunction "GPIO26_27") (pintype "unspecified+no_connect"))
    )
    (net (code "66") (name "unconnected-(U1-GPIO27-Pad28)") (class "Default")
      (node (ref "U1") (pin "28") (pinfunction "GPIO27_28") (pintype "unspecified+no_connect"))
    )
    (net (code "67") (name "unconnected-(U1-GPIO28-Pad36)") (class "Default")
      (node (ref "U1") (pin "36") (pinfunction "GPIO28_36") (pintype "unspecified+no_connect"))
    )
    (net (code "68") (name "unconnected-(U1-GPIO29-Pad37)") (class "Default")
      (node (ref "U1") (pin "37") (pinfunction "GPIO29_37") (pintype "unspecified+no_connect"))
    )
    (net (code "69") (name "unconnected-(U1-GPIO30-Pad38)") (class "Default")
      (node (ref "U1") (pin "38") (pinfunction "GPIO30_38") (pintype "unspecified+no_connect"))
    )
    (net (code "70") (name "unconnected-(U1-GPIO31-Pad39)") (class "Default")
      (node (ref "U1") (pin "39") (pinfunction "GPIO31_39") (pintype "unspecified+no_connect"))
    )
    (net (code "71") (name "unconnected-(U1-GPIO32-Pad40)") (class "Default")
      (node (ref "U1") (pin "40") (pinfunction "GPIO32_40") (pintype "unspecified+no_connect"))
    )
    (net (code "72") (name "unconnected-(U1-GPIO34-Pad43)") (class "Default")
      (node (ref "U1") (pin "43") (pinfunction "GPIO34_43") (pintype "unspecified+no_connect"))
    )
    (net (code "73") (name "unconnected-(U1-GPIO35-Pad44)") (class "Default")
      (node (ref "U1") (pin "44") (pinfunction "GPIO35_44") (pintype "unspecified+no_connect"))
    )
    (net (code "74") (name "unconnected-(U1-GPIO36-Pad45)") (class "Default")
      (node (ref "U1") (pin "45") (pinfunction "GPIO36_45") (pintype "unspecified+no_connect"))
    )
    (net (code "75") (name "unconnected-(U1-GPIO37-Pad46)") (class "Default")
      (node (ref "U1") (pin "46") (pinfunction "GPIO37_46") (pintype "unspecified+no_connect"))
    )
    (net (code "76") (name "unconnected-(U1-GPIO38-Pad47)") (class "Default")
      (node (ref "U1") (pin "47") (pinfunction "GPIO38_47") (pintype "unspecified+no_connect"))
    )
    (net (code "77") (name "unconnected-(U1-GPIO39-Pad48)") (class "Default")
      (node (ref "U1") (pin "48") (pinfunction "GPIO39_48") (pintype "unspecified+no_connect"))
    )
    (net (code "78") (name "unconnected-(USB1-SBU1-Pad9)") (class "Default")
      (node (ref "USB1") (pin "9") (pinfunction "SBU1_9") (pintype "unspecified+no_connect"))
    )
    (net (code "79") (name "unconnected-(USB1-SBU2-Pad3)") (class "Default")
      (node (ref "USB1") (pin "3") (pinfunction "SBU2_3") (pintype "unspecified+no_connect"))
    )
  )
)
